# OSSC_HDMI_Audio_v1_5_A3a.net
KiCad netlist of a schematic drawn in EAGLE
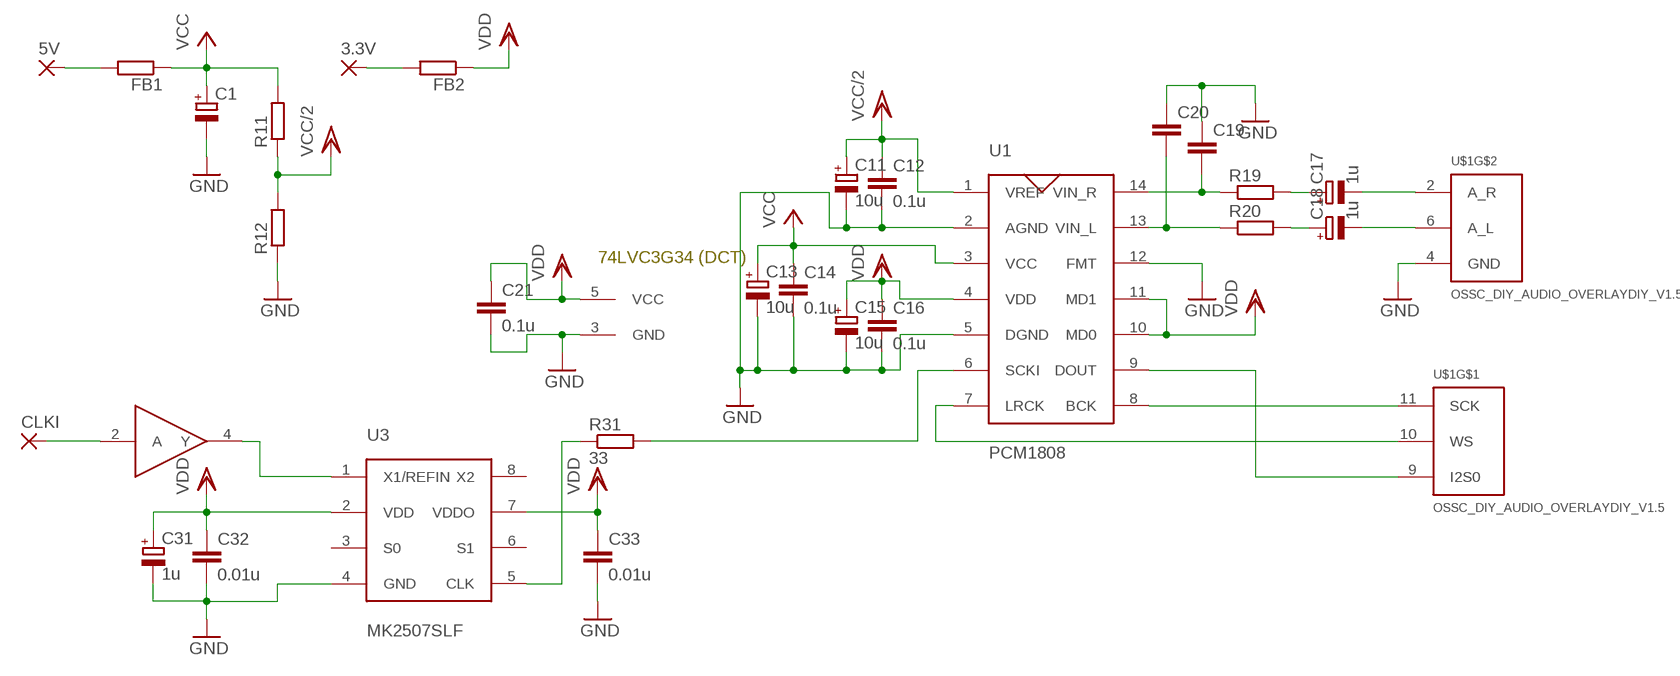
[diagram p0: schematic, sheet 1]

(export (version "E")
  (design (tool "Eeschema 10.0.6"))
  (components
    (comp (ref "3.3V")
      (value "SMD2")
      (footprint "eagle-import:SMD1,27-2,54")
      (libsource (lib "eagle-import") (part "SMD2"))
    )
    (comp (ref "5V")
      (value "SMD2")
      (footprint "eagle-import:SMD1,27-2,54")
      (libsource (lib "eagle-import") (part "SMD2"))
    )
    (comp (ref "C1")
      (value "CPOL-EUSMCC")
      (footprint "eagle-import:SMC_C")
      (libsource (lib "eagle-import") (part "CPOL-EUSMCC"))
    )
    (comp (ref "C11")
      (value "10u")
      (footprint "eagle-import:SMC_A")
      (libsource (lib "eagle-import") (part "CPOL-EUSMCA"))
    )
    (comp (ref "C12")
      (value "0.1u")
      (footprint "eagle-import:C0603")
      (libsource (lib "eagle-import") (part "C-EUC0603"))
    )
    (comp (ref "C13")
      (value "10u")
      (footprint "eagle-import:SMC_A")
      (libsource (lib "eagle-import") (part "CPOL-EUSMCA"))
    )
    (comp (ref "C14")
      (value "0.1u")
      (footprint "eagle-import:C0603")
      (libsource (lib "eagle-import") (part "C-EUC0603"))
    )
    (comp (ref "C15")
      (value "10u")
      (footprint "eagle-import:SMC_A")
      (libsource (lib "eagle-import") (part "CPOL-EUSMCA"))
    )
    (comp (ref "C16")
      (value "0.1u")
      (footprint "eagle-import:C0603")
      (libsource (lib "eagle-import") (part "C-EUC0603"))
    )
    (comp (ref "C17")
      (value "1u")
      (footprint "eagle-import:SMC_A")
      (libsource (lib "eagle-import") (part "CPOL-EUSMCA"))
    )
    (comp (ref "C18")
      (value "1u")
      (footprint "eagle-import:SMC_A")
      (libsource (lib "eagle-import") (part "CPOL-EUSMCA"))
    )
    (comp (ref "C19")
      (value "C-EUC0603")
      (footprint "eagle-import:C0603")
      (libsource (lib "eagle-import") (part "C-EUC0603"))
    )
    (comp (ref "C20")
      (value "C-EUC0603")
      (footprint "eagle-import:C0603")
      (libsource (lib "eagle-import") (part "C-EUC0603"))
    )
    (comp (ref "C21")
      (value "0.1u")
      (footprint "eagle-import:C0603")
      (libsource (lib "eagle-import") (part "C-EUC0603"))
    )
    (comp (ref "C31")
      (value "1u")
      (footprint "eagle-import:SMC_A")
      (libsource (lib "eagle-import") (part "CPOL-EUSMCA"))
    )
    (comp (ref "C32")
      (value "0.01u")
      (footprint "eagle-import:C0603")
      (libsource (lib "eagle-import") (part "C-EUC0603"))
    )
    (comp (ref "C33")
      (value "0.01u")
      (footprint "eagle-import:C0603")
      (libsource (lib "eagle-import") (part "C-EUC0603"))
    )
    (comp (ref "CLKI")
      (value "SMD2")
      (footprint "eagle-import:SMD1,27-2,54")
      (libsource (lib "eagle-import") (part "SMD2"))
    )
    (comp (ref "FB1")
      (value "R-EU_R0603")
      (footprint "eagle-import:R0603")
      (libsource (lib "eagle-import") (part "R-EU_R0603"))
    )
    (comp (ref "FB2")
      (value "R-EU_R0603")
      (footprint "eagle-import:R0603")
      (libsource (lib "eagle-import") (part "R-EU_R0603"))
    )
    (comp (ref "R11")
      (value "R-EU_R0603")
      (footprint "eagle-import:R0603")
      (libsource (lib "eagle-import") (part "R-EU_R0603"))
    )
    (comp (ref "R12")
      (value "R-EU_R0603")
      (footprint "eagle-import:R0603")
      (libsource (lib "eagle-import") (part "R-EU_R0603"))
    )
    (comp (ref "R19")
      (value "R-EU_R0603")
      (footprint "eagle-import:R0603")
      (libsource (lib "eagle-import") (part "R-EU_R0603"))
    )
    (comp (ref "R20")
      (value "R-EU_R0603")
      (footprint "eagle-import:R0603")
      (libsource (lib "eagle-import") (part "R-EU_R0603"))
    )
    (comp (ref "R31")
      (value "33")
      (footprint "eagle-import:R0603")
      (libsource (lib "eagle-import") (part "R-EU_R0603"))
    )
    (comp (ref "U$1")
      (value "OSSC_DIY_AUDIO_OVERLAYDIY_V1.5")
      (footprint "eagle-import:OSSC_OVERLAY_V1.5")
      (libsource (lib "eagle-import") (part "OSSC_DIY_AUDIO_OVERLAYDIY_V1.5"))
    )
    (comp (ref "U1")
      (value "PCM1808")
      (footprint "eagle-import:PCM1808")
      (libsource (lib "eagle-import") (part "PCM1808"))
    )
    (comp (ref "U2")
      (value "74LVC1G34")
      (footprint "eagle-import:74LVC1G34DCK")
      (libsource (lib "eagle-import") (part "74LVC1G34"))
    )
    (comp (ref "U3")
      (value "MK2507SLF")
      (footprint "eagle-import:SOIC8")
      (libsource (lib "eagle-import") (part "MK2507SLF"))
    )
  )
  (nets
    (net (code "1") (name "GND") (class "Default")
      (node (ref "C1") (pin "-") (pinfunction "-_-") (pintype "passive"))
      (node (ref "C11") (pin "-") (pinfunction "-_-") (pintype "passive"))
      (node (ref "C12") (pin "2") (pinfunction "2_2") (pintype "passive"))
      (node (ref "C13") (pin "-") (pinfunction "-_-") (pintype "passive"))
      (node (ref "C14") (pin "2") (pinfunction "2_2") (pintype "passive"))
      (node (ref "C15") (pin "-") (pinfunction "-_-") (pintype "passive"))
      (node (ref "C16") (pin "2") (pinfunction "2_2") (pintype "passive"))
      (node (ref "C19") (pin "1") (pinfunction "1_1") (pintype "passive"))
      (node (ref "C20") (pin "1") (pinfunction "1_1") (pintype "passive"))
      (node (ref "C21") (pin "2") (pinfunction "2_2") (pintype "passive"))
      (node (ref "C31") (pin "-") (pinfunction "-_-") (pintype "passive"))
      (node (ref "C32") (pin "2") (pinfunction "2_2") (pintype "passive"))
      (node (ref "C33") (pin "2") (pinfunction "2_2") (pintype "passive"))
      (node (ref "R12") (pin "1") (pinfunction "1_1") (pintype "passive"))
      (node (ref "U$1") (pin "4") (pinfunction "GND_4") (pintype "bidirectional"))
      (node (ref "U1") (pin "12") (pinfunction "FMT_12") (pintype "bidirectional"))
      (node (ref "U1") (pin "2") (pinfunction "AGND_2") (pintype "bidirectional"))
      (node (ref "U1") (pin "5") (pinfunction "DGND_5") (pintype "bidirectional"))
      (node (ref "U2") (pin "3") (pinfunction "GND_3") (pintype "bidirectional"))
      (node (ref "U3") (pin "4") (pinfunction "GND_4") (pintype "bidirectional"))
    )
    (net (code "2") (name "Net-(3.3V-P)") (class "Default")
      (node (ref "3.3V") (pin "1") (pinfunction "P_1") (pintype "passive"))
      (node (ref "FB2") (pin "2") (pinfunction "2_2") (pintype "passive"))
    )
    (net (code "3") (name "Net-(5V-P)") (class "Default")
      (node (ref "5V") (pin "1") (pinfunction "P_1") (pintype "passive"))
      (node (ref "FB1") (pin "2") (pinfunction "2_2") (pintype "passive"))
    )
    (net (code "4") (name "Net-(C17-Pad+)") (class "Default")
      (node (ref "C17") (pin "+") (pinfunction "+_+") (pintype "passive"))
      (node (ref "R19") (pin "2") (pinfunction "2_2") (pintype "passive"))
    )
    (net (code "5") (name "Net-(C18-Pad+)") (class "Default")
      (node (ref "C18") (pin "+") (pinfunction "+_+") (pintype "passive"))
      (node (ref "R20") (pin "2") (pinfunction "2_2") (pintype "passive"))
    )
    (net (code "6") (name "Net-(CLKI-P)") (class "Default")
      (node (ref "CLKI") (pin "1") (pinfunction "P_1") (pintype "passive"))
      (node (ref "U2") (pin "2") (pinfunction "A_2") (pintype "bidirectional"))
    )
    (net (code "7") (name "Net-(U$1A-I2S0)") (class "Default")
      (node (ref "U$1") (pin "9") (pinfunction "I2S0_9") (pintype "bidirectional"))
      (node (ref "U1") (pin "9") (pinfunction "DOUT_9") (pintype "bidirectional"))
    )
    (net (code "8") (name "Net-(U$1A-SCK)") (class "Default")
      (node (ref "U$1") (pin "11") (pinfunction "SCK_11") (pintype "bidirectional"))
      (node (ref "U1") (pin "8") (pinfunction "BCK_8") (pintype "bidirectional"))
    )
    (net (code "9") (name "Net-(U$1A-WS)") (class "Default")
      (node (ref "U$1") (pin "10") (pinfunction "WS_10") (pintype "bidirectional"))
      (node (ref "U1") (pin "7") (pinfunction "LRCK_7") (pintype "bidirectional"))
    )
    (net (code "10") (name "Net-(U$1B-A_L)") (class "Default")
      (node (ref "C18") (pin "-") (pinfunction "-_-") (pintype "passive"))
      (node (ref "U$1") (pin "6") (pinfunction "A_L_6") (pintype "bidirectional"))
    )
    (net (code "11") (name "Net-(U$1B-A_R)") (class "Default")
      (node (ref "C17") (pin "-") (pinfunction "-_-") (pintype "passive"))
      (node (ref "U$1") (pin "2") (pinfunction "A_R_2") (pintype "bidirectional"))
    )
    (net (code "12") (name "Net-(U1-SCKI)") (class "Default")
      (node (ref "R31") (pin "2") (pinfunction "2_2") (pintype "passive"))
      (node (ref "U1") (pin "6") (pinfunction "SCKI_6") (pintype "bidirectional"))
    )
    (net (code "13") (name "Net-(U1-VIN_L)") (class "Default")
      (node (ref "C20") (pin "2") (pinfunction "2_2") (pintype "passive"))
      (node (ref "R20") (pin "1") (pinfunction "1_1") (pintype "passive"))
      (node (ref "U1") (pin "13") (pinfunction "VIN_L_13") (pintype "bidirectional"))
    )
    (net (code "14") (name "Net-(U1-VIN_R)") (class "Default")
      (node (ref "C19") (pin "2") (pinfunction "2_2") (pintype "passive"))
      (node (ref "R19") (pin "1") (pinfunction "1_1") (pintype "passive"))
      (node (ref "U1") (pin "14") (pinfunction "VIN_R_14") (pintype "bidirectional"))
    )
    (net (code "15") (name "Net-(U2A-Y)") (class "Default")
      (node (ref "U2") (pin "4") (pinfunction "Y_4") (pintype "bidirectional"))
      (node (ref "U3") (pin "1") (pinfunction "X1/REFIN_1") (pintype "bidirectional"))
    )
    (net (code "16") (name "Net-(U3-CLK)") (class "Default")
      (node (ref "R31") (pin "1") (pinfunction "1_1") (pintype "passive"))
      (node (ref "U3") (pin "5") (pinfunction "CLK_5") (pintype "bidirectional"))
    )
    (net (code "17") (name "VCC") (class "Default")
      (node (ref "C1") (pin "+") (pinfunction "+_+") (pintype "passive"))
      (node (ref "C13") (pin "+") (pinfunction "+_+") (pintype "passive"))
      (node (ref "C14") (pin "1") (pinfunction "1_1") (pintype "passive"))
      (node (ref "FB1") (pin "1") (pinfunction "1_1") (pintype "passive"))
      (node (ref "R11") (pin "2") (pinfunction "2_2") (pintype "passive"))
      (node (ref "U1") (pin "3") (pinfunction "VCC_3") (pintype "bidirectional"))
    )
    (net (code "18") (name "VCC{slash}2") (class "Default")
      (node (ref "C11") (pin "+") (pinfunction "+_+") (pintype "passive"))
      (node (ref "C12") (pin "1") (pinfunction "1_1") (pintype "passive"))
      (node (ref "R11") (pin "1") (pinfunction "1_1") (pintype "passive"))
      (node (ref "R12") (pin "2") (pinfunction "2_2") (pintype "passive"))
      (node (ref "U1") (pin "1") (pinfunction "VREF_1") (pintype "bidirectional"))
    )
    (net (code "19") (name "VDD") (class "Default")
      (node (ref "C15") (pin "+") (pinfunction "+_+") (pintype "passive"))
      (node (ref "C16") (pin "1") (pinfunction "1_1") (pintype "passive"))
      (node (ref "C21") (pin "1") (pinfunction "1_1") (pintype "passive"))
      (node (ref "C31") (pin "+") (pinfunction "+_+") (pintype "passive"))
      (node (ref "C32") (pin "1") (pinfunction "1_1") (pintype "passive"))
      (node (ref "C33") (pin "1") (pinfunction "1_1") (pintype "passive"))
      (node (ref "FB2") (pin "1") (pinfunction "1_1") (pintype "passive"))
      (node (ref "U1") (pin "10") (pinfunction "MD0_10") (pintype "bidirectional"))
      (node (ref "U1") (pin "11") (pinfunction "MD1_11") (pintype "bidirectional"))
      (node (ref "U1") (pin "4") (pinfunction "VDD_4") (pintype "bidirectional"))
      (node (ref "U2") (pin "5") (pinfunction "VCC_5") (pintype "bidirectional"))
      (node (ref "U3") (pin "2") (pinfunction "VDD_2") (pintype "bidirectional"))
      (node (ref "U3") (pin "7") (pinfunction "VDDO_7") (pintype "bidirectional"))
    )
    (net (code "20") (name "unconnected-(U3-S0-Pad3)") (class "Default")
      (node (ref "U3") (pin "3") (pinfunction "S0_3") (pintype "bidirectional"))
    )
    (net (code "21") (name "unconnected-(U3-S1-Pad6)") (class "Default")
      (node (ref "U3") (pin "6") (pinfunction "S1_6") (pintype "bidirectional"))
    )
    (net (code "22") (name "unconnected-(U3-X2-Pad8)") (class "Default")
      (node (ref "U3") (pin "8") (pinfunction "X2_8") (pintype "bidirectional"))
    )
  )
)
